# SR1PCB_2024-12-18.net
KiCad netlist of a schematic drawn in Altium Designer
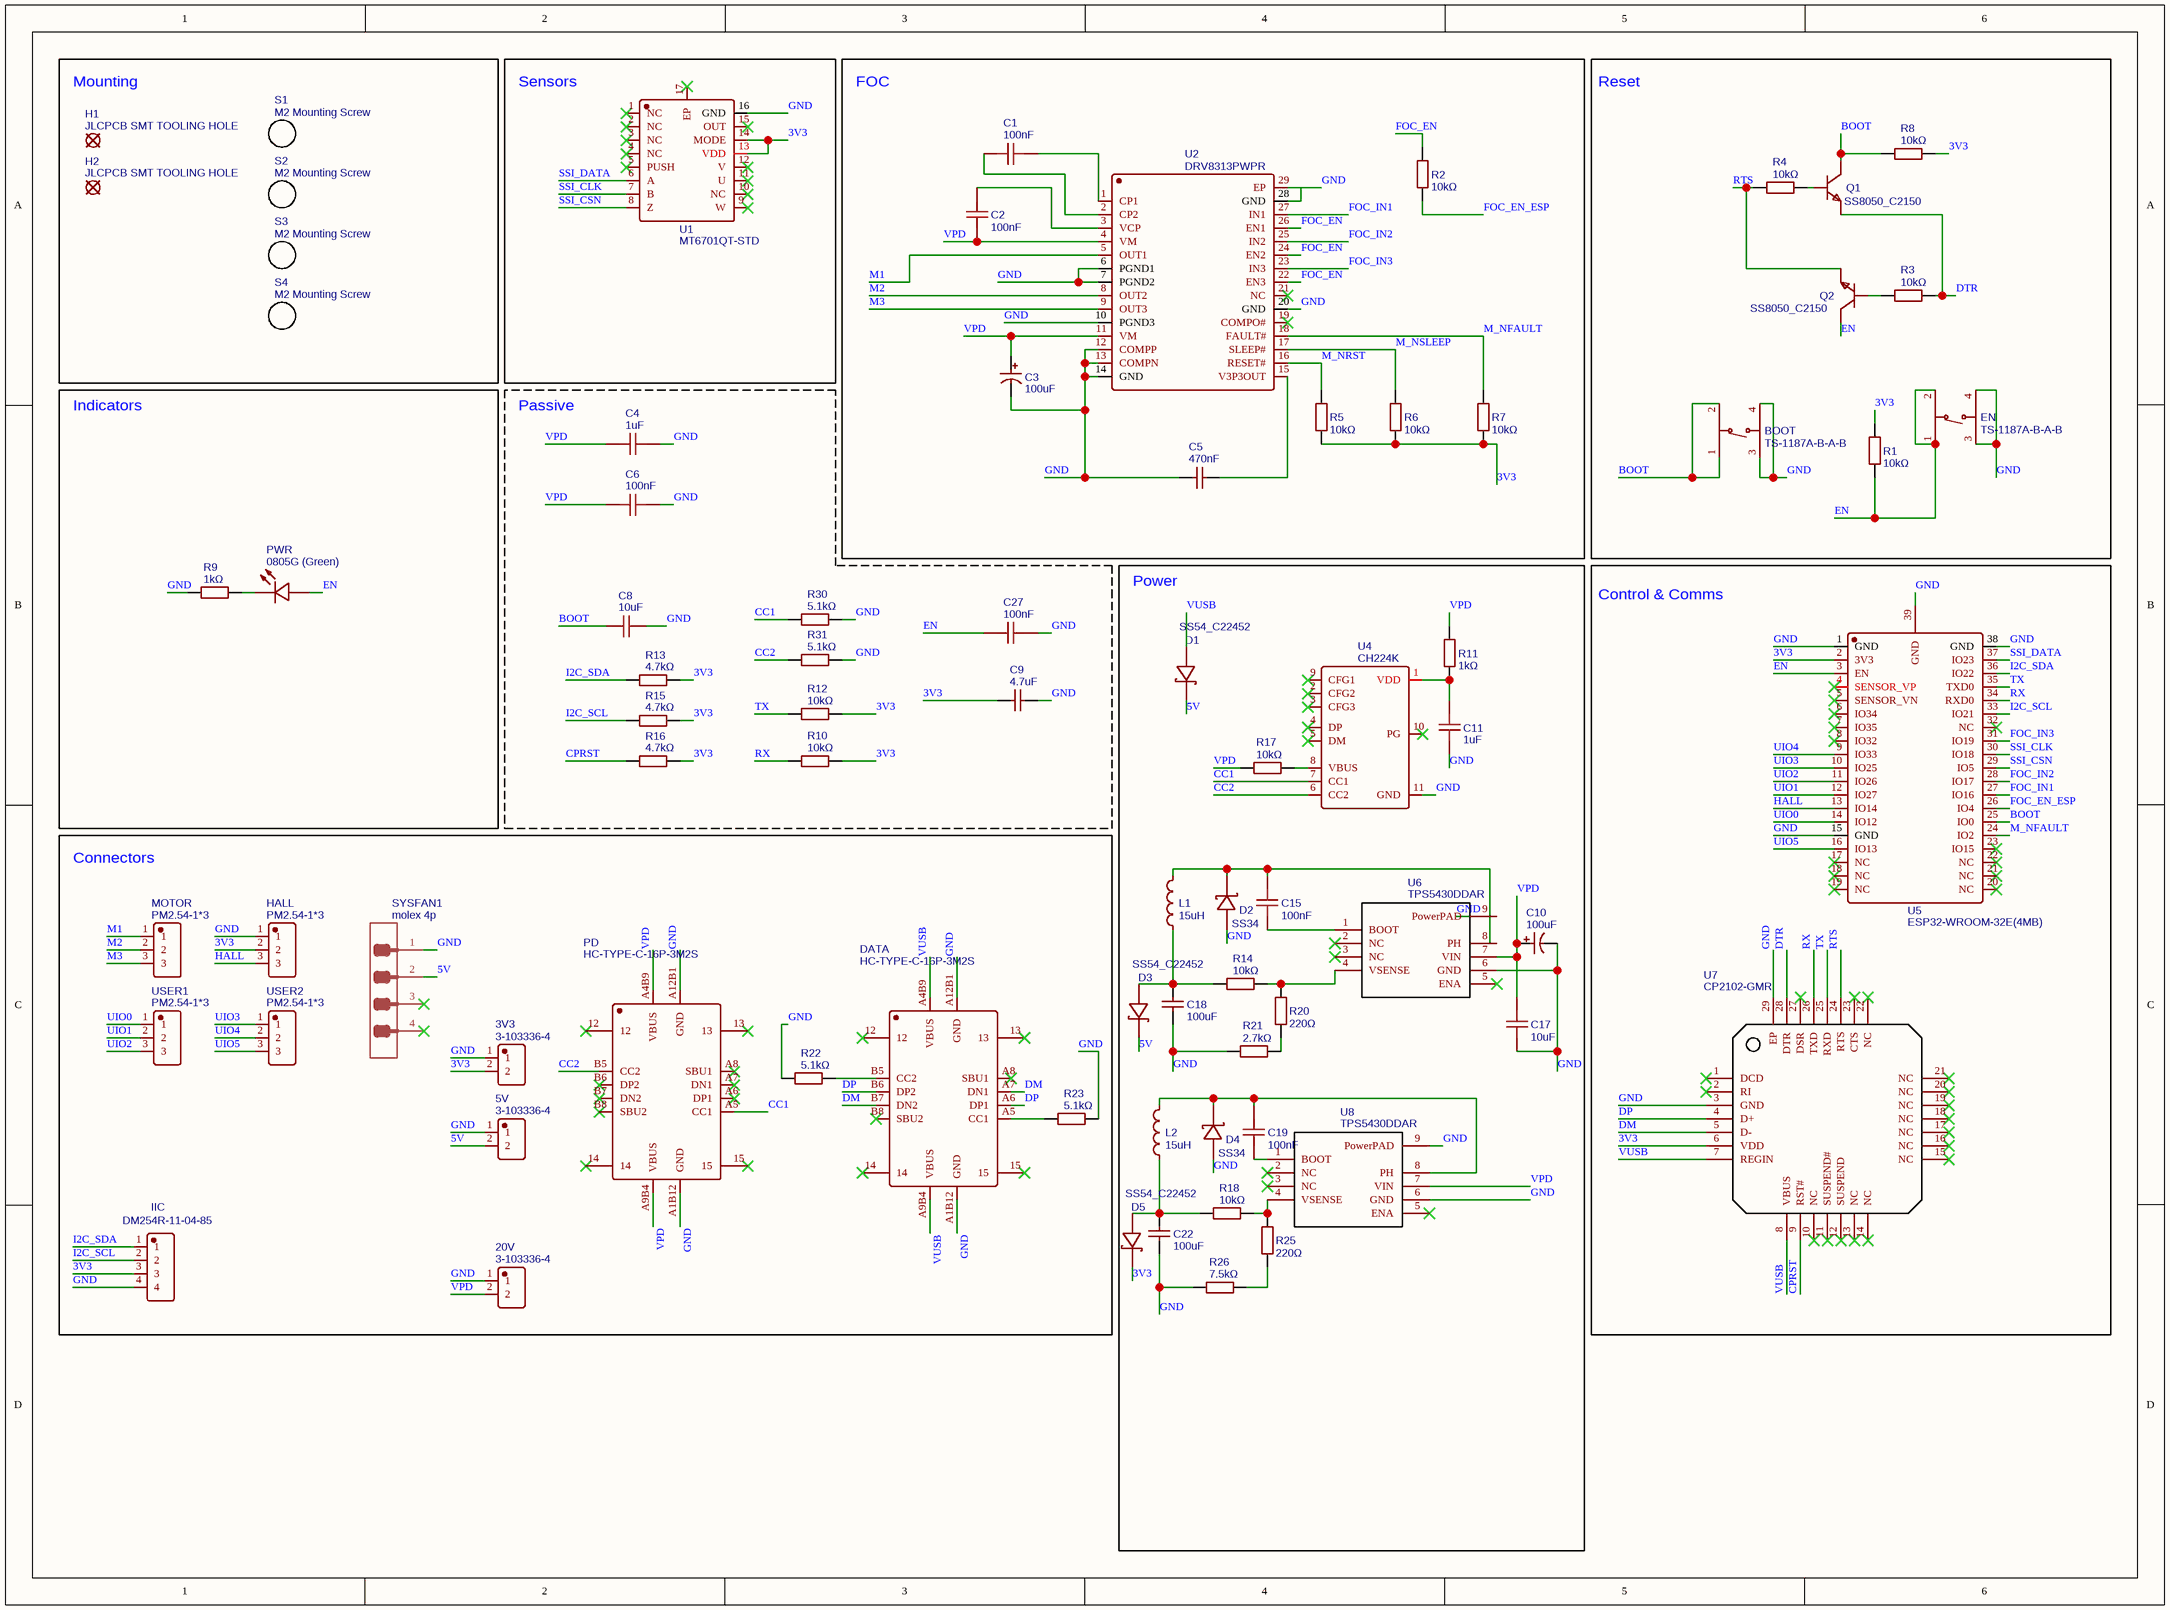
[diagram p0: SR1PCB_2024-12-18.schdoc]

(export (version "E")
  (design (tool "Eeschema 10.0.6"))
  (components
    (comp (ref "3V3")
      (value "3-103336-4")
      (fields (field (name "MANUFACTURER") "TE Connectivity(泰科电子)") (field (name "CONTRIBUTOR") "lcsc"))
      (libsource (lib "altium-import") (part "root_0_3-103336-4_"))
    )
    (comp (ref "5V")
      (value "3-103336-4")
      (fields (field (name "MANUFACTURER") "TE Connectivity(泰科电子)") (field (name "CONTRIBUTOR") "lcsc"))
      (libsource (lib "altium-import") (part "root_0_3-103336-4_"))
    )
    (comp (ref "20V")
      (value "3-103336-4")
      (fields (field (name "MANUFACTURER") "TE Connectivity(泰科电子)") (field (name "CONTRIBUTOR") "lcsc"))
      (libsource (lib "altium-import") (part "root_0_3-103336-4_"))
    )
    (comp (ref "BOOT")
      (value "TS-1187A-B-A-B")
      (fields (field (name "MANUFACTURER") "XKB Connectivity(中国星坤)") (field (name "CONTRIBUTOR") "LCSC"))
      (libsource (lib "altium-import") (part "root_1_TS-1187A-B-A-B_"))
    )
    (comp (ref "C1")
      (value "100nF")
      (fields
        (field (name "MANUFACTURER") "YAGEO(国巨)")
        (field (name "MANUFACTURER PART") "CC0603KRX7R9BB104")
      )
      (libsource (lib "altium-import") (part "root_0_100nF_"))
    )
    (comp (ref "C2")
      (value "100nF")
      (fields
        (field (name "MANUFACTURER") "YAGEO(国巨)")
        (field (name "MANUFACTURER PART") "CC0603KRX7R9BB104")
      )
      (libsource (lib "altium-import") (part "root_1_100nF_"))
    )
    (comp (ref "C3")
      (value "100uF")
      (fields
        (field (name "MANUFACTURER") "ROQANG(容强)")
        (field (name "MANUFACTURER PART") "RT1V101M0607")
        (field (name "CONTRIBUTOR") "LCSC")
      )
      (libsource (lib "altium-import") (part "root_3_100uF_"))
    )
    (comp (ref "C4")
      (value "1uF")
      (fields
        (field (name "MANUFACTURER PART") "CL10A105KB8NNNC")
        (field (name "MANUFACTURER") "SAMSUNG(三星)")
      )
      (libsource (lib "altium-import") (part "root_0_1uF_"))
    )
    (comp (ref "C5")
      (value "470nF")
      (fields
        (field (name "MANUFACTURER PART") "CL21B474KBFNNNE")
        (field (name "MANUFACTURER") "SAMSUNG(三星)")
        (field (name "CONTRIBUTOR") "eisendev")
      )
      (libsource (lib "altium-import") (part "root_3_470nF_"))
    )
    (comp (ref "C6")
      (value "100nF")
      (fields
        (field (name "MANUFACTURER") "YAGEO(国巨)")
        (field (name "MANUFACTURER PART") "CC0603KRX7R9BB104")
      )
      (libsource (lib "altium-import") (part "root_0_100nF_"))
    )
    (comp (ref "C8")
      (value "10uF")
      (fields
        (field (name "MANUFACTURER") "SAMSUNG(三星)")
        (field (name "MANUFACTURER PART") "CL10A106KP8NNNC")
        (field (name "CONTRIBUTOR") "kharchenko.pm")
      )
      (libsource (lib "altium-import") (part "root_0_10uF_"))
    )
    (comp (ref "C9")
      (value "4.7uF")
      (fields
        (field (name "MANUFACTURER PART") "CL05A475MP5NRNC")
        (field (name "MANUFACTURER") "SAMSUNG(三星)")
      )
      (libsource (lib "altium-import") (part "root_0_4.7uF_"))
    )
    (comp (ref "C10")
      (value "100uF")
      (fields
        (field (name "MANUFACTURER") "ROQANG(容强)")
        (field (name "MANUFACTURER PART") "RT1V101M0607")
        (field (name "CONTRIBUTOR") "LCSC")
      )
      (libsource (lib "altium-import") (part "root_0_100uF_"))
    )
    (comp (ref "C11")
      (value "1uF")
      (fields
        (field (name "MANUFACTURER PART") "CL10A105KB8NNNC")
        (field (name "MANUFACTURER") "SAMSUNG(三星)")
      )
      (libsource (lib "altium-import") (part "root_1_1uF_"))
    )
    (comp (ref "C15")
      (value "100nF")
      (fields
        (field (name "MANUFACTURER") "YAGEO(国巨)")
        (field (name "MANUFACTURER PART") "CC0603KRX7R9BB104")
      )
      (libsource (lib "altium-import") (part "root_3_100nF_"))
    )
    (comp (ref "C17")
      (value "10uF")
      (fields
        (field (name "MANUFACTURER PART") "CL21A106KAYNNNE")
        (field (name "MANUFACTURER") "SAMSUNG(三星)")
      )
      (libsource (lib "altium-import") (part "root_1_10uF_"))
    )
    (comp (ref "C18")
      (value "100uF")
      (fields
        (field (name "MANUFACTURER PART") "CL31A107MQHNNNE")
        (field (name "MANUFACTURER") "SAMSUNG(三星)")
      )
      (libsource (lib "altium-import") (part "root_1_100uF_"))
    )
    (comp (ref "C19")
      (value "100nF")
      (fields
        (field (name "MANUFACTURER") "YAGEO(国巨)")
        (field (name "MANUFACTURER PART") "CC0603KRX7R9BB104")
      )
      (libsource (lib "altium-import") (part "root_3_100nF_"))
    )
    (comp (ref "C22")
      (value "100uF")
      (fields
        (field (name "MANUFACTURER PART") "CL31A107MQHNNNE")
        (field (name "MANUFACTURER") "SAMSUNG(三星)")
      )
      (libsource (lib "altium-import") (part "root_1_100uF_"))
    )
    (comp (ref "C27")
      (value "100nF")
      (fields
        (field (name "MANUFACTURER") "YAGEO(国巨)")
        (field (name "MANUFACTURER PART") "CC0603KRX7R9BB104")
      )
      (libsource (lib "altium-import") (part "root_0_100nF_"))
    )
    (comp (ref "D1")
      (value "SS54_C22452")
      (fields
        (field (name "MANUFACTURER PART") "SS54")
        (field (name "MANUFACTURER") "MDD")
        (field (name "CONTRIBUTOR") "mtz8302")
      )
      (libsource (lib "altium-import") (part "root_3_SS54_C22452_"))
    )
    (comp (ref "D2")
      (value "SS34")
      (fields (field (name "MANUFACTURER") "MDD(辰达半导体)"))
      (libsource (lib "altium-import") (part "root_3_SS34_"))
    )
    (comp (ref "D3")
      (value "SS54_C22452")
      (fields
        (field (name "MANUFACTURER PART") "SS54")
        (field (name "MANUFACTURER") "MDD")
        (field (name "CONTRIBUTOR") "mtz8302")
      )
      (libsource (lib "altium-import") (part "root_3_SS54_C22452_"))
    )
    (comp (ref "D4")
      (value "SS34")
      (fields (field (name "MANUFACTURER") "MDD(辰达半导体)"))
      (libsource (lib "altium-import") (part "root_3_SS34_"))
    )
    (comp (ref "D5")
      (value "SS54_C22452")
      (fields
        (field (name "MANUFACTURER PART") "SS54")
        (field (name "MANUFACTURER") "MDD")
        (field (name "CONTRIBUTOR") "mtz8302")
      )
      (libsource (lib "altium-import") (part "root_3_SS54_C22452_"))
    )
    (comp (ref "DATA")
      (value "HC-TYPE-C-16P-3M2S")
      (fields (field (name "MANUFACTURER") "HC(虹成电子)") (field (name "CONTRIBUTOR") "lcsc"))
      (libsource (lib "altium-import") (part "root_0_HC-TYPE-C-16P-3M2S_"))
    )
    (comp (ref "EN")
      (value "TS-1187A-B-A-B")
      (fields (field (name "MANUFACTURER") "XKB Connectivity(中国星坤)") (field (name "CONTRIBUTOR") "LCSC"))
      (libsource (lib "altium-import") (part "root_1_TS-1187A-B-A-B_"))
    )
    (comp (ref "H1")
      (value "JLCPCB SMT TOOLING HOLE")
      (fields (field (name "CONTRIBUTOR") "Sindel90"))
      (libsource (lib "altium-import") (part "root_0_JLCPCB SMT TOOLING HOLE_"))
    )
    (comp (ref "H2")
      (value "JLCPCB SMT TOOLING HOLE")
      (fields (field (name "CONTRIBUTOR") "Sindel90"))
      (libsource (lib "altium-import") (part "root_0_JLCPCB SMT TOOLING HOLE_"))
    )
    (comp (ref "HALL")
      (value "PM2.54-1*3")
      (fields (field (name "MANUFACTURER") "ZHOURI(洲日)") (field (name "CONTRIBUTOR") "lcsc"))
      (libsource (lib "altium-import") (part "root_0_PM2.54-1*3_"))
    )
    (comp (ref "IIC")
      (value "DM254R-11-04-85")
      (fields (field (name "MANUFACTURER") "DEALON(德艺隆)") (field (name "CONTRIBUTOR") "LCSC"))
      (libsource (lib "altium-import") (part "root_0_DM254R-11-04-85_"))
    )
    (comp (ref "L1")
      (value "15uH")
      (fields
        (field (name "MANUFACTURER") "Sunlord(顺络)")
        (field (name "MANUFACTURER PART") "MWSA0603S-150MT")
        (field (name "CONTRIBUTOR") "LCSC")
      )
      (libsource (lib "altium-import") (part "root_1_15uH_"))
    )
    (comp (ref "L2")
      (value "15uH")
      (fields
        (field (name "MANUFACTURER") "Sunlord(顺络)")
        (field (name "MANUFACTURER PART") "MWSA0603S-150MT")
        (field (name "CONTRIBUTOR") "LCSC")
      )
      (libsource (lib "altium-import") (part "root_1_15uH_"))
    )
    (comp (ref "MOTOR")
      (value "PM2.54-1*3")
      (fields (field (name "MANUFACTURER") "ZHOURI(洲日)") (field (name "CONTRIBUTOR") "lcsc"))
      (libsource (lib "altium-import") (part "root_0_PM2.54-1*3_"))
    )
    (comp (ref "PD")
      (value "HC-TYPE-C-16P-3M2S")
      (fields (field (name "MANUFACTURER") "HC(虹成电子)") (field (name "CONTRIBUTOR") "lcsc"))
      (libsource (lib "altium-import") (part "root_0_HC-TYPE-C-16P-3M2S_"))
    )
    (comp (ref "PWR")
      (value "0805G (Green)")
      (fields (field (name "MANUFACTURER") "KENTO") (field (name "MANUFACTURER PART") "KT-0805G"))
      (libsource (lib "altium-import") (part "root_0_0805G (Green)_"))
    )
    (comp (ref "Q1")
      (value "SS8050_C2150")
      (fields (field (name "MANUFACTURER") "CJ(江苏长电/长晶)") (field (name "MANUFACTURER PART") "SS8050"))
      (libsource (lib "altium-import") (part "root_0_SS8050_C2150_"))
    )
    (comp (ref "Q2")
      (value "SS8050_C2150")
      (fields (field (name "MANUFACTURER") "CJ(江苏长电/长晶)") (field (name "MANUFACTURER PART") "SS8050"))
      (libsource (lib "altium-import") (part "root_2_SS8050_C2150_"))
    )
    (comp (ref "R1")
      (value "10kΩ")
      (fields
        (field (name "MANUFACTURER") "UNI-ROYAL(厚声)")
        (field (name "MANUFACTURER PART") "0402WGF1002TCE")
      )
      (libsource (lib "altium-import") (part "root_1_10kΩ_"))
    )
    (comp (ref "R2")
      (value "10kΩ")
      (fields (field (name "MANUFACTURER") "UniOhm") (field (name "MANUFACTURER PART") "0603WAF4701T5E"))
      (libsource (lib "altium-import") (part "root_1_10kΩ_"))
    )
    (comp (ref "R3")
      (value "10kΩ")
      (fields
        (field (name "MANUFACTURER") "UNI-ROYAL(厚声)")
        (field (name "MANUFACTURER PART") "0402WGF1002TCE")
      )
      (libsource (lib "altium-import") (part "root_2_10kΩ_"))
    )
    (comp (ref "R4")
      (value "10kΩ")
      (fields
        (field (name "MANUFACTURER") "UNI-ROYAL(厚声)")
        (field (name "MANUFACTURER PART") "0402WGF1002TCE")
      )
      (libsource (lib "altium-import") (part "root_2_10kΩ_"))
    )
    (comp (ref "R5")
      (value "10kΩ")
      (fields
        (field (name "MANUFACTURER") "UNI-ROYAL(厚声)")
        (field (name "MANUFACTURER PART") "0402WGF1002TCE")
      )
      (libsource (lib "altium-import") (part "root_1_10kΩ_"))
    )
    (comp (ref "R6")
      (value "10kΩ")
      (fields
        (field (name "MANUFACTURER") "UNI-ROYAL(厚声)")
        (field (name "MANUFACTURER PART") "0402WGF1002TCE")
      )
      (libsource (lib "altium-import") (part "root_1_10kΩ_"))
    )
    (comp (ref "R7")
      (value "10kΩ")
      (fields
        (field (name "MANUFACTURER") "UNI-ROYAL(厚声)")
        (field (name "MANUFACTURER PART") "0402WGF1002TCE")
      )
      (libsource (lib "altium-import") (part "root_1_10kΩ_"))
    )
    (comp (ref "R8")
      (value "10kΩ")
      (fields
        (field (name "MANUFACTURER") "UNI-ROYAL(厚声)")
        (field (name "MANUFACTURER PART") "0402WGF1002TCE")
      )
      (libsource (lib "altium-import") (part "root_2_10kΩ_"))
    )
    (comp (ref "R9")
      (value "1kΩ")
      (fields
        (field (name "MANUFACTURER") "UNI-ROYAL(厚声)")
        (field (name "MANUFACTURER PART") "0402WGF1001TCE")
      )
      (libsource (lib "altium-import") (part "root_2_1kΩ_"))
    )
    (comp (ref "R10")
      (value "10kΩ")
      (fields
        (field (name "MANUFACTURER") "UNI-ROYAL(厚声)")
        (field (name "MANUFACTURER PART") "0402WGF1002TCE")
      )
      (libsource (lib "altium-import") (part "root_0_10kΩ_"))
    )
    (comp (ref "R11")
      (value "1kΩ")
      (fields
        (field (name "MANUFACTURER") "UNI-ROYAL(厚声)")
        (field (name "MANUFACTURER PART") "0402WGF1001TCE")
      )
      (libsource (lib "altium-import") (part "root_1_1kΩ_"))
    )
    (comp (ref "R12")
      (value "10kΩ")
      (fields
        (field (name "MANUFACTURER") "UNI-ROYAL(厚声)")
        (field (name "MANUFACTURER PART") "0402WGF1002TCE")
      )
      (libsource (lib "altium-import") (part "root_0_10kΩ_"))
    )
    (comp (ref "R13")
      (value "4.7kΩ")
      (fields
        (field (name "MANUFACTURER") "UNI-ROYAL(厚声)")
        (field (name "MANUFACTURER PART") "0402WGF4701TCE")
      )
      (libsource (lib "altium-import") (part "root_0_4.7kΩ_"))
    )
    (comp (ref "R14")
      (value "10kΩ")
      (fields
        (field (name "MANUFACTURER") "UNI-ROYAL(厚声)")
        (field (name "MANUFACTURER PART") "0402WGF1002TCE")
      )
      (libsource (lib "altium-import") (part "root_0_10kΩ_"))
    )
    (comp (ref "R15")
      (value "4.7kΩ")
      (fields
        (field (name "MANUFACTURER") "UNI-ROYAL(厚声)")
        (field (name "MANUFACTURER PART") "0402WGF4701TCE")
      )
      (libsource (lib "altium-import") (part "root_0_4.7kΩ_"))
    )
    (comp (ref "R16")
      (value "4.7kΩ")
      (fields
        (field (name "MANUFACTURER") "UNI-ROYAL(厚声)")
        (field (name "MANUFACTURER PART") "0402WGF4701TCE")
      )
      (libsource (lib "altium-import") (part "root_0_4.7kΩ_"))
    )
    (comp (ref "R17")
      (value "10kΩ")
      (fields
        (field (name "MANUFACTURER") "UNI-ROYAL(厚声)")
        (field (name "MANUFACTURER PART") "0402WGF1002TCE")
      )
      (libsource (lib "altium-import") (part "root_2_10kΩ_"))
    )
    (comp (ref "R18")
      (value "10kΩ")
      (fields
        (field (name "MANUFACTURER") "UNI-ROYAL(厚声)")
        (field (name "MANUFACTURER PART") "0402WGF1002TCE")
      )
      (libsource (lib "altium-import") (part "root_0_10kΩ_"))
    )
    (comp (ref "R20")
      (value "220Ω")
      (fields
        (field (name "MANUFACTURER") "UNI-ROYAL(厚声)")
        (field (name "MANUFACTURER PART") "0603WAF2200T5E")
      )
      (libsource (lib "altium-import") (part "root_1_220Ω_"))
    )
    (comp (ref "R21")
      (value "2.7kΩ")
      (fields
        (field (name "MANUFACTURER") "UniOhm")
        (field (name "MANUFACTURER PART") "0603WAF2701T5E")
        (field (name "CONTRIBUTOR") "kliu24")
      )
      (libsource (lib "altium-import") (part "root_0_2.7kΩ_"))
    )
    (comp (ref "R22")
      (value "5.1kΩ")
      (fields
        (field (name "MANUFACTURER") "UNI-ROYAL(厚声)")
        (field (name "MANUFACTURER PART") "0402WGF5101TCE")
      )
      (libsource (lib "altium-import") (part "root_0_5.1kΩ_"))
    )
    (comp (ref "R23")
      (value "5.1kΩ")
      (fields
        (field (name "MANUFACTURER") "UNI-ROYAL(厚声)")
        (field (name "MANUFACTURER PART") "0402WGF5101TCE")
      )
      (libsource (lib "altium-import") (part "root_0_5.1kΩ_"))
    )
    (comp (ref "R25")
      (value "220Ω")
      (fields
        (field (name "MANUFACTURER") "UNI-ROYAL(厚声)")
        (field (name "MANUFACTURER PART") "0603WAF2200T5E")
      )
      (libsource (lib "altium-import") (part "root_1_220Ω_"))
    )
    (comp (ref "R26")
      (value "7.5kΩ")
      (fields
        (field (name "MANUFACTURER") "UniOhm")
        (field (name "MANUFACTURER PART") "0603WAF7501T5E")
        (field (name "CONTRIBUTOR") "kliu24")
      )
      (libsource (lib "altium-import") (part "root_1_7.5kΩ_"))
    )
    (comp (ref "R30")
      (value "5.1kΩ")
      (fields
        (field (name "MANUFACTURER") "UNI-ROYAL(厚声)")
        (field (name "MANUFACTURER PART") "0402WGF5101TCE")
      )
      (libsource (lib "altium-import") (part "root_0_5.1kΩ_"))
    )
    (comp (ref "R31")
      (value "5.1kΩ")
      (fields
        (field (name "MANUFACTURER") "UNI-ROYAL(厚声)")
        (field (name "MANUFACTURER PART") "0402WGF5101TCE")
      )
      (libsource (lib "altium-import") (part "root_0_5.1kΩ_"))
    )
    (comp (ref "S1")
      (value "M2 Mounting Screw")
      (fields (field (name "CONTRIBUTOR") "Dayat -"))
      (libsource (lib "altium-import") (part "root_0_M2 Mounting Screw_"))
    )
    (comp (ref "S2")
      (value "M2 Mounting Screw")
      (fields (field (name "CONTRIBUTOR") "Dayat -"))
      (libsource (lib "altium-import") (part "root_0_M2 Mounting Screw_"))
    )
    (comp (ref "S3")
      (value "M2 Mounting Screw")
      (fields (field (name "CONTRIBUTOR") "Dayat -"))
      (libsource (lib "altium-import") (part "root_0_M2 Mounting Screw_"))
    )
    (comp (ref "S4")
      (value "M2 Mounting Screw")
      (fields (field (name "CONTRIBUTOR") "Dayat -"))
      (libsource (lib "altium-import") (part "root_0_M2 Mounting Screw_"))
    )
    (comp (ref "SYSFAN1")
      (value "molex 4p")
      (fields (field (name "CONTRIBUTOR") "delil1220"))
      (libsource (lib "altium-import") (part "root_0_molex 4p_"))
    )
    (comp (ref "U1")
      (value "MT6701QT-STD")
      (fields (field (name "MANUFACTURER") "MagnTek(麦歌恩)") (field (name "CONTRIBUTOR") "LCSC"))
      (libsource (lib "altium-import") (part "root_0_MT6701QT-STD_"))
    )
    (comp (ref "U2")
      (value "DRV8313PWPR")
      (fields (field (name "MANUFACTURER") "Texas Instruments") (field (name "CONTRIBUTOR") "LCSC"))
      (libsource (lib "altium-import") (part "root_0_DRV8313PWPR_"))
    )
    (comp (ref "U4")
      (value "CH224K")
      (fields (field (name "MANUFACTURER") "WCH(南京沁恒)") (field (name "CONTRIBUTOR") "lcsc"))
      (libsource (lib "altium-import") (part "root_0_CH224K_"))
    )
    (comp (ref "U5")
      (value "ESP32-WROOM-32E(4MB)")
      (fields
        (field (name "MANUFACTURER") "ESPRESSIF(乐鑫)")
        (field (name "MANUFACTURER PART") "ESP32-WROOM-32E-N4")
        (field (name "CONTRIBUTOR") "LCSC")
      )
      (libsource (lib "altium-import") (part "root_0_ESP32-WROOM-32E(4MB)_"))
    )
    (comp (ref "U6")
      (value "TPS5430DDAR")
      (fields (field (name "MANUFACTURER") "TI(德州仪器)"))
      (libsource (lib "altium-import") (part "root_0_TPS5430DDAR_"))
    )
    (comp (ref "U7")
      (value "CP2102-GMR")
      (fields (field (name "MANUFACTURER") "SKYWORKS/SILICON LABS(芯科)"))
      (libsource (lib "altium-import") (part "root_0_CP2102-GMR_"))
    )
    (comp (ref "U8")
      (value "TPS5430DDAR")
      (fields (field (name "MANUFACTURER") "TI(德州仪器)"))
      (libsource (lib "altium-import") (part "root_0_TPS5430DDAR_"))
    )
    (comp (ref "USER1")
      (value "PM2.54-1*3")
      (fields (field (name "MANUFACTURER") "ZHOURI(洲日)") (field (name "CONTRIBUTOR") "lcsc"))
      (libsource (lib "altium-import") (part "root_0_PM2.54-1*3_"))
    )
    (comp (ref "USER2")
      (value "PM2.54-1*3")
      (fields (field (name "MANUFACTURER") "ZHOURI(洲日)") (field (name "CONTRIBUTOR") "lcsc"))
      (libsource (lib "altium-import") (part "root_0_PM2.54-1*3_"))
    )
  )
  (nets
    (net (code "1") (name "/3V3") (class "Default")
      (node (ref "3V3") (pin "2") (pinfunction "2_2") (pintype "passive"))
      (node (ref "C9") (pin "1") (pinfunction "1_1") (pintype "passive"))
      (node (ref "D5") (pin "2") (pinfunction "K_2") (pintype "passive"))
      (node (ref "HALL") (pin "2") (pinfunction "2_2") (pintype "passive"))
      (node (ref "IIC") (pin "3") (pinfunction "3_3") (pintype "passive"))
      (node (ref "R1") (pin "2") (pinfunction "2_2") (pintype "passive"))
      (node (ref "R10") (pin "2") (pinfunction "2_2") (pintype "passive"))
      (node (ref "R12") (pin "2") (pinfunction "2_2") (pintype "passive"))
      (node (ref "R13") (pin "2") (pinfunction "2_2") (pintype "passive"))
      (node (ref "R15") (pin "2") (pinfunction "2_2") (pintype "passive"))
      (node (ref "R16") (pin "2") (pinfunction "2_2") (pintype "passive"))
      (node (ref "R5") (pin "1") (pinfunction "1_1") (pintype "passive"))
      (node (ref "R6") (pin "1") (pinfunction "1_1") (pintype "passive"))
      (node (ref "R7") (pin "1") (pinfunction "1_1") (pintype "passive"))
      (node (ref "R8") (pin "1") (pinfunction "1_1") (pintype "passive"))
      (node (ref "U1") (pin "13") (pinfunction "VDD_13") (pintype "passive"))
      (node (ref "U1") (pin "14") (pinfunction "MODE_14") (pintype "passive"))
      (node (ref "U5") (pin "2") (pinfunction "3V3_2") (pintype "passive"))
      (node (ref "U7") (pin "6") (pinfunction "VDD_6") (pintype "passive"))
    )
    (net (code "2") (name "/5V") (class "Default")
      (node (ref "5V") (pin "2") (pinfunction "2_2") (pintype "passive"))
      (node (ref "D1") (pin "2") (pinfunction "K_2") (pintype "passive"))
      (node (ref "D3") (pin "2") (pinfunction "K_2") (pintype "passive"))
      (node (ref "SYSFAN1") (pin "2") (pinfunction "2_2") (pintype "passive"))
    )
    (net (code "3") (name "/BOOT") (class "Default")
      (node (ref "BOOT") (pin "1") (pinfunction "A_1") (pintype "passive"))
      (node (ref "BOOT") (pin "2") (pinfunction "B_2") (pintype "passive"))
      (node (ref "C8") (pin "1") (pinfunction "1_1") (pintype "passive"))
      (node (ref "Q1") (pin "3") (pinfunction "C_3") (pintype "passive"))
      (node (ref "R8") (pin "2") (pinfunction "2_2") (pintype "passive"))
      (node (ref "U5") (pin "25") (pinfunction "IO0_25") (pintype "passive"))
    )
    (net (code "4") (name "/CC1") (class "Default")
      (node (ref "PD") (pin "A5") (pinfunction "CC1_A5") (pintype "passive"))
      (node (ref "R30") (pin "1") (pinfunction "1_1") (pintype "passive"))
      (node (ref "U4") (pin "7") (pinfunction "CC1_7") (pintype "passive"))
    )
    (net (code "5") (name "/CC2") (class "Default")
      (node (ref "PD") (pin "B5") (pinfunction "CC2_B5") (pintype "passive"))
      (node (ref "R31") (pin "1") (pinfunction "1_1") (pintype "passive"))
      (node (ref "U4") (pin "6") (pinfunction "CC2_6") (pintype "passive"))
    )
    (net (code "6") (name "/CPRST") (class "Default")
      (node (ref "R16") (pin "1") (pinfunction "1_1") (pintype "passive"))
      (node (ref "U7") (pin "9") (pinfunction "RST#_9") (pintype "passive"))
    )
    (net (code "7") (name "/DM") (class "Default")
      (node (ref "DATA") (pin "A7") (pinfunction "DN1_A7") (pintype "passive"))
      (node (ref "DATA") (pin "B7") (pinfunction "DN2_B7") (pintype "passive"))
      (node (ref "U7") (pin "5") (pinfunction "D-_5") (pintype "passive"))
    )
    (net (code "8") (name "/DP") (class "Default")
      (node (ref "DATA") (pin "A6") (pinfunction "DP1_A6") (pintype "passive"))
      (node (ref "DATA") (pin "B6") (pinfunction "DP2_B6") (pintype "passive"))
      (node (ref "U7") (pin "4") (pinfunction "D+_4") (pintype "passive"))
    )
    (net (code "9") (name "/DTR") (class "Default")
      (node (ref "Q1") (pin "2") (pinfunction "E_2") (pintype "passive"))
      (node (ref "R3") (pin "1") (pinfunction "1_1") (pintype "passive"))
      (node (ref "U7") (pin "28") (pinfunction "DTR_28") (pintype "passive"))
    )
    (net (code "10") (name "/EN") (class "Default")
      (node (ref "C27") (pin "1") (pinfunction "1_1") (pintype "passive"))
      (node (ref "EN") (pin "1") (pinfunction "A_1") (pintype "passive"))
      (node (ref "EN") (pin "2") (pinfunction "B_2") (pintype "passive"))
      (node (ref "PWR") (pin "1") (pinfunction "A_1") (pintype "passive"))
      (node (ref "Q2") (pin "3") (pinfunction "C_3") (pintype "passive"))
      (node (ref "R1") (pin "1") (pinfunction "1_1") (pintype "passive"))
      (node (ref "U5") (pin "3") (pinfunction "EN_3") (pintype "passive"))
    )
    (net (code "11") (name "/FOC_EN") (class "Default")
      (node (ref "R2") (pin "2") (pinfunction "2_2") (pintype "passive"))
      (node (ref "U2") (pin "22") (pinfunction "EN3_22") (pintype "passive"))
      (node (ref "U2") (pin "24") (pinfunction "EN2_24") (pintype "passive"))
      (node (ref "U2") (pin "26") (pinfunction "EN1_26") (pintype "passive"))
    )
    (net (code "12") (name "/FOC_EN_ESP") (class "Default")
      (node (ref "R2") (pin "1") (pinfunction "1_1") (pintype "passive"))
      (node (ref "U5") (pin "26") (pinfunction "IO4_26") (pintype "passive"))
    )
    (net (code "13") (name "/FOC_IN1") (class "Default")
      (node (ref "U2") (pin "27") (pinfunction "IN1_27") (pintype "passive"))
      (node (ref "U5") (pin "27") (pinfunction "IO16_27") (pintype "passive"))
    )
    (net (code "14") (name "/FOC_IN2") (class "Default")
      (node (ref "U2") (pin "25") (pinfunction "IN2_25") (pintype "passive"))
      (node (ref "U5") (pin "28") (pinfunction "IO17_28") (pintype "passive"))
    )
    (net (code "15") (name "/FOC_IN3") (class "Default")
      (node (ref "U2") (pin "23") (pinfunction "IN3_23") (pintype "passive"))
      (node (ref "U5") (pin "31") (pinfunction "IO19_31") (pintype "passive"))
    )
    (net (code "16") (name "/GND") (class "Default")
      (node (ref "20V") (pin "1") (pinfunction "1_1") (pintype "passive"))
      (node (ref "3V3") (pin "1") (pinfunction "1_1") (pintype "passive"))
      (node (ref "5V") (pin "1") (pinfunction "1_1") (pintype "passive"))
      (node (ref "BOOT") (pin "3") (pinfunction "C_3") (pintype "passive"))
      (node (ref "BOOT") (pin "4") (pinfunction "D_4") (pintype "passive"))
      (node (ref "C10") (pin "2") (pinfunction "2_2") (pintype "passive"))
      (node (ref "C11") (pin "1") (pinfunction "1_1") (pintype "passive"))
      (node (ref "C17") (pin "1") (pinfunction "1_1") (pintype "passive"))
      (node (ref "C18") (pin "1") (pinfunction "1_1") (pintype "passive"))
      (node (ref "C22") (pin "1") (pinfunction "1_1") (pintype "passive"))
      (node (ref "C27") (pin "2") (pinfunction "2_2") (pintype "passive"))
      (node (ref "C3") (pin "2") (pinfunction "2_2") (pintype "passive"))
      (node (ref "C4") (pin "2") (pinfunction "2_2") (pintype "passive"))
      (node (ref "C5") (pin "1") (pinfunction "1_1") (pintype "passive"))
      (node (ref "C6") (pin "2") (pinfunction "2_2") (pintype "passive"))
      (node (ref "C8") (pin "2") (pinfunction "2_2") (pintype "passive"))
      (node (ref "C9") (pin "2") (pinfunction "2_2") (pintype "passive"))
      (node (ref "D2") (pin "2") (pinfunction "A_2") (pintype "passive"))
      (node (ref "D4") (pin "2") (pinfunction "A_2") (pintype "passive"))
      (node (ref "DATA") (pin "A12B1") (pinfunction "GND_A12B1") (pintype "passive"))
      (node (ref "DATA") (pin "A1B12") (pinfunction "GND_A1B12") (pintype "passive"))
      (node (ref "EN") (pin "3") (pinfunction "C_3") (pintype "passive"))
      (node (ref "EN") (pin "4") (pinfunction "D_4") (pintype "passive"))
      (node (ref "HALL") (pin "1") (pinfunction "1_1") (pintype "passive"))
      (node (ref "IIC") (pin "4") (pinfunction "4_4") (pintype "passive"))
      (node (ref "PD") (pin "A12B1") (pinfunction "GND_A12B1") (pintype "passive"))
      (node (ref "PD") (pin "A1B12") (pinfunction "GND_A1B12") (pintype "passive"))
      (node (ref "R21") (pin "2") (pinfunction "2_2") (pintype "passive"))
      (node (ref "R22") (pin "1") (pinfunction "1_1") (pintype "passive"))
      (node (ref "R23") (pin "2") (pinfunction "2_2") (pintype "passive"))
      (node (ref "R26") (pin "2") (pinfunction "2_2") (pintype "passive"))
      (node (ref "R30") (pin "2") (pinfunction "2_2") (pintype "passive"))
      (node (ref "R31") (pin "2") (pinfunction "2_2") (pintype "passive"))
      (node (ref "R9") (pin "2") (pinfunction "2_2") (pintype "passive"))
      (node (ref "SYSFAN1") (pin "1") (pinfunction "1_1") (pintype "passive"))
      (node (ref "U1") (pin "16") (pinfunction "GND_16") (pintype "passive"))
      (node (ref "U2") (pin "10") (pinfunction "PGND3_10") (pintype "passive"))
      (node (ref "U2") (pin "12") (pinfunction "COMPP_12") (pintype "passive"))
      (node (ref "U2") (pin "13") (pinfunction "COMPN_13") (pintype "passive"))
      (node (ref "U2") (pin "14") (pinfunction "GND_14") (pintype "passive"))
      (node (ref "U2") (pin "20") (pinfunction "GND_20") (pintype "passive"))
      (node (ref "U2") (pin "28") (pinfunction "GND_28") (pintype "passive"))
      (node (ref "U2") (pin "29") (pinfunction "EP_29") (pintype "passive"))
      (node (ref "U2") (pin "6") (pinfunction "PGND1_6") (pintype "passive"))
      (node (ref "U2") (pin "7") (pinfunction "PGND2_7") (pintype "passive"))
      (node (ref "U4") (pin "11") (pinfunction "GND_11") (pintype "passive"))
      (node (ref "U5") (pin "1") (pinfunction "GND_1") (pintype "passive"))
      (node (ref "U5") (pin "15") (pinfunction "GND_15") (pintype "passive"))
      (node (ref "U5") (pin "38") (pinfunction "GND_38") (pintype "passive"))
      (node (ref "U5") (pin "39") (pinfunction "GND_39") (pintype "passive"))
      (node (ref "U6") (pin "6") (pinfunction "GND_6") (pintype "passive"))
      (node (ref "U6") (pin "9") (pinfunction "PowerPAD_9") (pintype "passive"))
      (node (ref "U7") (pin "29") (pinfunction "EP_29") (pintype "passive"))
      (node (ref "U7") (pin "3") (pinfunction "GND_3") (pintype "passive"))
      (node (ref "U8") (pin "6") (pinfunction "GND_6") (pintype "passive"))
      (node (ref "U8") (pin "9") (pinfunction "PowerPAD_9") (pintype "passive"))
    )
    (net (code "17") (name "/HALL") (class "Default")
      (node (ref "HALL") (pin "3") (pinfunction "3_3") (pintype "passive"))
      (node (ref "U5") (pin "13") (pinfunction "IO14_13") (pintype "passive"))
    )
    (net (code "18") (name "/I2C_SCL") (class "Default")
      (node (ref "IIC") (pin "2") (pinfunction "2_2") (pintype "passive"))
      (node (ref "R15") (pin "1") (pinfunction "1_1") (pintype "passive"))
      (node (ref "U5") (pin "33") (pinfunction "IO21_33") (pintype "passive"))
    )
    (net (code "19") (name "/I2C_SDA") (class "Default")
      (node (ref "IIC") (pin "1") (pinfunction "1_1") (pintype "passive"))
      (node (ref "R13") (pin "1") (pinfunction "1_1") (pintype "passive"))
      (node (ref "U5") (pin "36") (pinfunction "IO22_36") (pintype "passive"))
    )
    (net (code "20") (name "/M1") (class "Default")
      (node (ref "MOTOR") (pin "1") (pinfunction "1_1") (pintype "passive"))
      (node (ref "U2") (pin "5") (pinfunction "OUT1_5") (pintype "passive"))
    )
    (net (code "21") (name "/M2") (class "Default")
      (node (ref "MOTOR") (pin "2") (pinfunction "2_2") (pintype "passive"))
      (node (ref "U2") (pin "8") (pinfunction "OUT2_8") (pintype "passive"))
    )
    (net (code "22") (name "/M3") (class "Default")
      (node (ref "MOTOR") (pin "3") (pinfunction "3_3") (pintype "passive"))
      (node (ref "U2") (pin "9") (pinfunction "OUT3_9") (pintype "passive"))
    )
    (net (code "23") (name "/M_NFAULT") (class "Default")
      (node (ref "R7") (pin "2") (pinfunction "2_2") (pintype "passive"))
      (node (ref "U2") (pin "18") (pinfunction "FAULT#_18") (pintype "passive"))
      (node (ref "U5") (pin "24") (pinfunction "IO2_24") (pintype "passive"))
    )
    (net (code "24") (name "/M_NRST") (class "Default")
      (node (ref "R5") (pin "2") (pinfunction "2_2") (pintype "passive"))
      (node (ref "U2") (pin "16") (pinfunction "RESET#_16") (pintype "passive"))
    )
    (net (code "25") (name "/M_NSLEEP") (class "Default")
      (node (ref "R6") (pin "2") (pinfunction "2_2") (pintype "passive"))
      (node (ref "U2") (pin "17") (pinfunction "SLEEP#_17") (pintype "passive"))
    )
    (net (code "26") (name "/RTS") (class "Default")
      (node (ref "Q2") (pin "2") (pinfunction "E_2") (pintype "passive"))
      (node (ref "R4") (pin "2") (pinfunction "2_2") (pintype "passive"))
      (node (ref "U7") (pin "24") (pinfunction "RTS_24") (pintype "passive"))
    )
    (net (code "27") (name "/RX") (class "Default")
      (node (ref "R10") (pin "1") (pinfunction "1_1") (pintype "passive"))
      (node (ref "U5") (pin "34") (pinfunction "RXD0_34") (pintype "passive"))
      (node (ref "U7") (pin "26") (pinfunction "TXD_26") (pintype "passive"))
    )
    (net (code "28") (name "/SSI_CLK") (class "Default")
      (node (ref "U1") (pin "7") (pinfunction "B_7") (pintype "passive"))
      (node (ref "U5") (pin "30") (pinfunction "IO18_30") (pintype "passive"))
    )
    (net (code "29") (name "/SSI_CSN") (class "Default")
      (node (ref "U1") (pin "8") (pinfunction "Z_8") (pintype "passive"))
      (node (ref "U5") (pin "29") (pinfunction "IO5_29") (pintype "passive"))
    )
    (net (code "30") (name "/SSI_DATA") (class "Default")
      (node (ref "U1") (pin "6") (pinfunction "A_6") (pintype "passive"))
      (node (ref "U5") (pin "37") (pinfunction "IO23_37") (pintype "passive"))
    )
    (net (code "31") (name "/TX") (class "Default")
      (node (ref "R12") (pin "1") (pinfunction "1_1") (pintype "passive"))
      (node (ref "U5") (pin "35") (pinfunction "TXD0_35") (pintype "passive"))
      (node (ref "U7") (pin "25") (pinfunction "RXD_25") (pintype "passive"))
    )
    (net (code "32") (name "/UIO0") (class "Default")
      (node (ref "U5") (pin "14") (pinfunction "IO12_14") (pintype "passive"))
      (node (ref "USER1") (pin "1") (pinfunction "1_1") (pintype "passive"))
    )
    (net (code "33") (name "/UIO1") (class "Default")
      (node (ref "U5") (pin "12") (pinfunction "IO27_12") (pintype "passive"))
      (node (ref "USER1") (pin "2") (pinfunction "2_2") (pintype "passive"))
    )
    (net (code "34") (name "/UIO2") (class "Default")
      (node (ref "U5") (pin "11") (pinfunction "IO26_11") (pintype "passive"))
      (node (ref "USER1") (pin "3") (pinfunction "3_3") (pintype "passive"))
    )
    (net (code "35") (name "/UIO3") (class "Default")
      (node (ref "U5") (pin "10") (pinfunction "IO25_10") (pintype "passive"))
      (node (ref "USER2") (pin "1") (pinfunction "1_1") (pintype "passive"))
    )
    (net (code "36") (name "/UIO4") (class "Default")
      (node (ref "U5") (pin "9") (pinfunction "IO33_9") (pintype "passive"))
      (node (ref "USER2") (pin "2") (pinfunction "2_2") (pintype "passive"))
    )
    (net (code "37") (name "/UIO5") (class "Default")
      (node (ref "U5") (pin "16") (pinfunction "IO13_16") (pintype "passive"))
      (node (ref "USER2") (pin "3") (pinfunction "3_3") (pintype "passive"))
    )
    (net (code "38") (name "/VPD") (class "Default")
      (node (ref "20V") (pin "2") (pinfunction "2_2") (pintype "passive"))
      (node (ref "C10") (pin "1") (pinfunction "1_1") (pintype "passive"))
      (node (ref "C17") (pin "2") (pinfunction "2_2") (pintype "passive"))
      (node (ref "C2") (pin "1") (pinfunction "1_1") (pintype "passive"))
      (node (ref "C3") (pin "1") (pinfunction "1_1") (pintype "passive"))
      (node (ref "C4") (pin "1") (pinfunction "1_1") (pintype "passive"))
      (node (ref "C6") (pin "1") (pinfunction "1_1") (pintype "passive"))
      (node (ref "PD") (pin "A4B9") (pinfunction "VBUS_A4B9") (pintype "passive"))
      (node (ref "PD") (pin "A9B4") (pinfunction "VBUS_A9B4") (pintype "passive"))
      (node (ref "R11") (pin "2") (pinfunction "2_2") (pintype "passive"))
      (node (ref "R17") (pin "2") (pinfunction "2_2") (pintype "passive"))
      (node (ref "U2") (pin "11") (pinfunction "VM_11") (pintype "passive"))
      (node (ref "U2") (pin "4") (pinfunction "VM_4") (pintype "passive"))
      (node (ref "U6") (pin "7") (pinfunction "VIN_7") (pintype "passive"))
      (node (ref "U8") (pin "7") (pinfunction "VIN_7") (pintype "passive"))
    )
    (net (code "39") (name "/VUSB") (class "Default")
      (node (ref "D1") (pin "1") (pinfunction "A_1") (pintype "passive"))
      (node (ref "DATA") (pin "A4B9") (pinfunction "VBUS_A4B9") (pintype "passive"))
      (node (ref "DATA") (pin "A9B4") (pinfunction "VBUS_A9B4") (pintype "passive"))
      (node (ref "U7") (pin "7") (pinfunction "REGIN_7") (pintype "passive"))
      (node (ref "U7") (pin "8") (pinfunction "VBUS_8") (pintype "passive"))
    )
    (net (code "40") (name "Net-(D2-K)") (class "Default")
      (node (ref "C15") (pin "1") (pinfunction "1_1") (pintype "passive"))
      (node (ref "D2") (pin "1") (pinfunction "K_1") (pintype "passive"))
      (node (ref "L1") (pin "2") (pinfunction "2_2") (pintype "passive"))
      (node (ref "U6") (pin "8") (pinfunction "PH_8") (pintype "passive"))
    )
    (net (code "41") (name "Net-(D3-A)") (class "Default")
      (node (ref "C18") (pin "2") (pinfunction "2_2") (pintype "passive"))
      (node (ref "D3") (pin "1") (pinfunction "A_1") (pintype "passive"))
      (node (ref "L1") (pin "1") (pinfunction "1_1") (pintype "passive"))
      (node (ref "R14") (pin "1") (pinfunction "1_1") (pintype "passive"))
    )
    (net (code "42") (name "Net-(D4-K)") (class "Default")
      (node (ref "C19") (pin "1") (pinfunction "1_1") (pintype "passive"))
      (node (ref "D4") (pin "1") (pinfunction "K_1") (pintype "passive"))
      (node (ref "L2") (pin "2") (pinfunction "2_2") (pintype "passive"))
      (node (ref "U8") (pin "8") (pinfunction "PH_8") (pintype "passive"))
    )
    (net (code "43") (name "Net-(D5-A)") (class "Default")
      (node (ref "C22") (pin "2") (pinfunction "2_2") (pintype "passive"))
      (node (ref "D5") (pin "1") (pinfunction "A_1") (pintype "passive"))
      (node (ref "L2") (pin "1") (pinfunction "1_1") (pintype "passive"))
      (node (ref "R18") (pin "1") (pinfunction "1_1") (pintype "passive"))
    )
    (net (code "44") (name "Net-(DATA-CC1)") (class "Default")
      (node (ref "DATA") (pin "A5") (pinfunction "CC1_A5") (pintype "passive"))
      (node (ref "R23") (pin "1") (pinfunction "1_1") (pintype "passive"))
    )
    (net (code "45") (name "Net-(DATA-CC2)") (class "Default")
      (node (ref "DATA") (pin "B5") (pinfunction "CC2_B5") (pintype "passive"))
      (node (ref "R22") (pin "2") (pinfunction "2_2") (pintype "passive"))
    )
    (net (code "46") (name "Net-(PWR-K)") (class "Default")
      (node (ref "PWR") (pin "2") (pinfunction "K_2") (pintype "passive"))
      (node (ref "R9") (pin "1") (pinfunction "1_1") (pintype "passive"))
    )
    (net (code "47") (name "Net-(Q1-B)") (class "Default")
      (node (ref "Q1") (pin "1") (pinfunction "B_1") (pintype "passive"))
      (node (ref "R4") (pin "1") (pinfunction "1_1") (pintype "passive"))
    )
    (net (code "48") (name "Net-(Q2-B)") (class "Default")
      (node (ref "Q2") (pin "1") (pinfunction "B_1") (pintype "passive"))
      (node (ref "R3") (pin "2") (pinfunction "2_2") (pintype "passive"))
    )
    (net (code "49") (name "Net-(R20-Pad1)") (class "Default")
      (node (ref "R20") (pin "1") (pinfunction "1_1") (pintype "passive"))
      (node (ref "R21") (pin "1") (pinfunction "1_1") (pintype "passive"))
    )
    (net (code "50") (name "Net-(R25-Pad1)") (class "Default")
      (node (ref "R25") (pin "1") (pinfunction "1_1") (pintype "passive"))
      (node (ref "R26") (pin "1") (pinfunction "1_1") (pintype "passive"))
    )
    (net (code "51") (name "Net-(U2-CP1)") (class "Default")
      (node (ref "C1") (pin "2") (pinfunction "2_2") (pintype "passive"))
      (node (ref "U2") (pin "1") (pinfunction "CP1_1") (pintype "passive"))
    )
    (net (code "52") (name "Net-(U2-CP2)") (class "Default")
      (node (ref "C1") (pin "1") (pinfunction "1_1") (pintype "passive"))
      (node (ref "U2") (pin "2") (pinfunction "CP2_2") (pintype "passive"))
    )
    (net (code "53") (name "Net-(U2-V3P3OUT)") (class "Default")
      (node (ref "C5") (pin "2") (pinfunction "2_2") (pintype "passive"))
      (node (ref "U2") (pin "15") (pinfunction "V3P3OUT_15") (pintype "passive"))
    )
    (net (code "54") (name "Net-(U2-VCP)") (class "Default")
      (node (ref "C2") (pin "2") (pinfunction "2_2") (pintype "passive"))
      (node (ref "U2") (pin "3") (pinfunction "VCP_3") (pintype "passive"))
    )
    (net (code "55") (name "Net-(U4-VBUS)") (class "Default")
      (node (ref "R17") (pin "1") (pinfunction "1_1") (pintype "passive"))
      (node (ref "U4") (pin "8") (pinfunction "VBUS_8") (pintype "passive"))
    )
    (net (code "56") (name "Net-(U4-VDD)") (class "Default")
      (node (ref "C11") (pin "2") (pinfunction "2_2") (pintype "passive"))
      (node (ref "R11") (pin "1") (pinfunction "1_1") (pintype "passive"))
      (node (ref "U4") (pin "1") (pinfunction "VDD_1") (pintype "passive"))
    )
    (net (code "57") (name "Net-(U6-BOOT)") (class "Default")
      (node (ref "C15") (pin "2") (pinfunction "2_2") (pintype "passive"))
      (node (ref "U6") (pin "1") (pinfunction "BOOT_1") (pintype "passive"))
    )
    (net (code "58") (name "Net-(U6-VSENSE)") (class "Default")
      (node (ref "R14") (pin "2") (pinfunction "2_2") (pintype "passive"))
      (node (ref "R20") (pin "2") (pinfunction "2_2") (pintype "passive"))
      (node (ref "U6") (pin "4") (pinfunction "VSENSE_4") (pintype "passive"))
    )
    (net (code "59") (name "Net-(U8-BOOT)") (class "Default")
      (node (ref "C19") (pin "2") (pinfunction "2_2") (pintype "passive"))
      (node (ref "U8") (pin "1") (pinfunction "BOOT_1") (pintype "passive"))
    )
    (net (code "60") (name "Net-(U8-VSENSE)") (class "Default")
      (node (ref "R18") (pin "2") (pinfunction "2_2") (pintype "passive"))
      (node (ref "R25") (pin "2") (pinfunction "2_2") (pintype "passive"))
      (node (ref "U8") (pin "4") (pinfunction "VSENSE_4") (pintype "passive"))
    )
    (net (code "61") (name "unconnected-(DATA-Pad12)") (class "Default")
      (node (ref "DATA") (pin "12") (pinfunction "12_12") (pintype "passive+no_connect"))
    )
    (net (code "62") (name "unconnected-(DATA-Pad13)") (class "Default")
      (node (ref "DATA") (pin "13") (pinfunction "13_13") (pintype "passive+no_connect"))
    )
    (net (code "63") (name "unconnected-(DATA-Pad14)") (class "Default")
      (node (ref "DATA") (pin "14") (pinfunction "14_14") (pintype "passive+no_connect"))
    )
    (net (code "64") (name "unconnected-(DATA-Pad15)") (class "Default")
      (node (ref "DATA") (pin "15") (pinfunction "15_15") (pintype "passive+no_connect"))
    )
    (net (code "65") (name "unconnected-(DATA-SBU1-PadA8)") (class "Default")
      (node (ref "DATA") (pin "A8") (pinfunction "SBU1_A8") (pintype "passive+no_connect"))
    )
    (net (code "66") (name "unconnected-(DATA-SBU2-PadB8)") (class "Default")
      (node (ref "DATA") (pin "B8") (pinfunction "SBU2_B8") (pintype "passive+no_connect"))
    )
    (net (code "67") (name "unconnected-(PD-DN1-PadA7)") (class "Default")
      (node (ref "PD") (pin "A7") (pinfunction "DN1_A7") (pintype "passive+no_connect"))
    )
    (net (code "68") (name "unconnected-(PD-DN2-PadB7)") (class "Default")
      (node (ref "PD") (pin "B7") (pinfunction "DN2_B7") (pintype "passive+no_connect"))
    )
    (net (code "69") (name "unconnected-(PD-DP1-PadA6)") (class "Default")
      (node (ref "PD") (pin "A6") (pinfunction "DP1_A6") (pintype "passive+no_connect"))
    )
    (net (code "70") (name "unconnected-(PD-DP2-PadB6)") (class "Default")
      (node (ref "PD") (pin "B6") (pinfunction "DP2_B6") (pintype "passive+no_connect"))
    )
    (net (code "71") (name "unconnected-(PD-Pad12)") (class "Default")
      (node (ref "PD") (pin "12") (pinfunction "12_12") (pintype "passive+no_connect"))
    )
    (net (code "72") (name "unconnected-(PD-Pad13)") (class "Default")
      (node (ref "PD") (pin "13") (pinfunction "13_13") (pintype "passive+no_connect"))
    )
    (net (code "73") (name "unconnected-(PD-Pad14)") (class "Default")
      (node (ref "PD") (pin "14") (pinfunction "14_14") (pintype "passive+no_connect"))
    )
    (net (code "74") (name "unconnected-(PD-Pad15)") (class "Default")
      (node (ref "PD") (pin "15") (pinfunction "15_15") (pintype "passive+no_connect"))
    )
    (net (code "75") (name "unconnected-(PD-SBU1-PadA8)") (class "Default")
      (node (ref "PD") (pin "A8") (pinfunction "SBU1_A8") (pintype "passive+no_connect"))
    )
    (net (code "76") (name "unconnected-(PD-SBU2-PadB8)") (class "Default")
      (node (ref "PD") (pin "B8") (pinfunction "SBU2_B8") (pintype "passive+no_connect"))
    )
    (net (code "77") (name "unconnected-(SYSFAN1-Pad3)") (class "Default")
      (node (ref "SYSFAN1") (pin "3") (pinfunction "3_3") (pintype "passive+no_connect"))
    )
    (net (code "78") (name "unconnected-(SYSFAN1-Pad4)") (class "Default")
      (node (ref "SYSFAN1") (pin "4") (pinfunction "4_4") (pintype "passive+no_connect"))
    )
    (net (code "79") (name "unconnected-(U1-EP-Pad17)") (class "Default")
      (node (ref "U1") (pin "17") (pinfunction "EP_17") (pintype "passive+no_connect"))
    )
    (net (code "80") (name "unconnected-(U1-NC-Pad1)") (class "Default")
      (node (ref "U1") (pin "1") (pinfunction "NC_1") (pintype "passive+no_connect"))
    )
    (net (code "81") (name "unconnected-(U1-NC-Pad2)") (class "Default")
      (node (ref "U1") (pin "2") (pinfunction "NC_2") (pintype "passive+no_connect"))
    )
    (net (code "82") (name "unconnected-(U1-NC-Pad3)") (class "Default")
      (node (ref "U1") (pin "3") (pinfunction "NC_3") (pintype "passive+no_connect"))
    )
    (net (code "83") (name "unconnected-(U1-NC-Pad4)") (class "Default")
      (node (ref "U1") (pin "4") (pinfunction "NC_4") (pintype "passive+no_connect"))
    )
    (net (code "84") (name "unconnected-(U1-NC-Pad10)") (class "Default")
      (node (ref "U1") (pin "10") (pinfunction "NC_10") (pintype "passive+no_connect"))
    )
    (net (code "85") (name "unconnected-(U1-OUT-Pad15)") (class "Default")
      (node (ref "U1") (pin "15") (pinfunction "OUT_15") (pintype "passive+no_connect"))
    )
    (net (code "86") (name "unconnected-(U1-PUSH-Pad5)") (class "Default")
      (node (ref "U1") (pin "5") (pinfunction "PUSH_5") (pintype "passive+no_connect"))
    )
    (net (code "87") (name "unconnected-(U1-U-Pad11)") (class "Default")
      (node (ref "U1") (pin "11") (pinfunction "U_11") (pintype "passive+no_connect"))
    )
    (net (code "88") (name "unconnected-(U1-V-Pad12)") (class "Default")
      (node (ref "U1") (pin "12") (pinfunction "V_12") (pintype "passive+no_connect"))
    )
    (net (code "89") (name "unconnected-(U1-W-Pad9)") (class "Default")
      (node (ref "U1") (pin "9") (pinfunction "W_9") (pintype "passive+no_connect"))
    )
    (net (code "90") (name "unconnected-(U2-COMPO#-Pad19)") (class "Default")
      (node (ref "U2") (pin "19") (pinfunction "COMPO#_19") (pintype "passive+no_connect"))
    )
    (net (code "91") (name "unconnected-(U2-NC-Pad21)") (class "Default")
      (node (ref "U2") (pin "21") (pinfunction "NC_21") (pintype "passive+no_connect"))
    )
    (net (code "92") (name "unconnected-(U4-CFG1-Pad9)") (class "Default")
      (node (ref "U4") (pin "9") (pinfunction "CFG1_9") (pintype "passive+no_connect"))
    )
    (net (code "93") (name "unconnected-(U4-CFG2-Pad2)") (class "Default")
      (node (ref "U4") (pin "2") (pinfunction "CFG2_2") (pintype "passive+no_connect"))
    )
    (net (code "94") (name "unconnected-(U4-CFG3-Pad3)") (class "Default")
      (node (ref "U4") (pin "3") (pinfunction "CFG3_3") (pintype "passive+no_connect"))
    )
    (net (code "95") (name "unconnected-(U4-DM-Pad5)") (class "Default")
      (node (ref "U4") (pin "5") (pinfunction "DM_5") (pintype "passive+no_connect"))
    )
    (net (code "96") (name "unconnected-(U4-DP-Pad4)") (class "Default")
      (node (ref "U4") (pin "4") (pinfunction "DP_4") (pintype "passive+no_connect"))
    )
    (net (code "97") (name "unconnected-(U4-PG-Pad10)") (class "Default")
      (node (ref "U4") (pin "10") (pinfunction "PG_10") (pintype "passive+no_connect"))
    )
    (net (code "98") (name "unconnected-(U5-IO15-Pad23)") (class "Default")
      (node (ref "U5") (pin "23") (pinfunction "IO15_23") (pintype "passive+no_connect"))
    )
    (net (code "99") (name "unconnected-(U5-IO32-Pad8)") (class "Default")
      (node (ref "U5") (pin "8") (pinfunction "IO32_8") (pintype "passive+no_connect"))
    )
    (net (code "100") (name "unconnected-(U5-IO34-Pad6)") (class "Default")
      (node (ref "U5") (pin "6") (pinfunction "IO34_6") (pintype "passive+no_connect"))
    )
    (net (code "101") (name "unconnected-(U5-IO35-Pad7)") (class "Default")
      (node (ref "U5") (pin "7") (pinfunction "IO35_7") (pintype "passive+no_connect"))
    )
    (net (code "102") (name "unconnected-(U5-NC-Pad17)") (class "Default")
      (node (ref "U5") (pin "17") (pinfunction "NC_17") (pintype "passive+no_connect"))
    )
    (net (code "103") (name "unconnected-(U5-NC-Pad18)") (class "Default")
      (node (ref "U5") (pin "18") (pinfunction "NC_18") (pintype "passive+no_connect"))
    )
    (net (code "104") (name "unconnected-(U5-NC-Pad19)") (class "Default")
      (node (ref "U5") (pin "19") (pinfunction "NC_19") (pintype "passive+no_connect"))
    )
    (net (code "105") (name "unconnected-(U5-NC-Pad20)") (class "Default")
      (node (ref "U5") (pin "20") (pinfunction "NC_20") (pintype "passive+no_connect"))
    )
    (net (code "106") (name "unconnected-(U5-NC-Pad21)") (class "Default")
      (node (ref "U5") (pin "21") (pinfunction "NC_21") (pintype "passive+no_connect"))
    )
    (net (code "107") (name "unconnected-(U5-NC-Pad22)") (class "Default")
      (node (ref "U5") (pin "22") (pinfunction "NC_22") (pintype "passive+no_connect"))
    )
    (net (code "108") (name "unconnected-(U5-NC-Pad32)") (class "Default")
      (node (ref "U5") (pin "32") (pinfunction "NC_32") (pintype "passive+no_connect"))
    )
    (net (code "109") (name "unconnected-(U5-SENSOR_VN-Pad5)") (class "Default")
      (node (ref "U5") (pin "5") (pinfunction "SENSOR_VN_5") (pintype "passive+no_connect"))
    )
    (net (code "110") (name "unconnected-(U5-SENSOR_VP-Pad4)") (class "Default")
      (node (ref "U5") (pin "4") (pinfunction "SENSOR_VP_4") (pintype "passive+no_connect"))
    )
    (net (code "111") (name "unconnected-(U6-ENA-Pad5)") (class "Default")
      (node (ref "U6") (pin "5") (pinfunction "ENA_5") (pintype "passive+no_connect"))
    )
    (net (code "112") (name "unconnected-(U6-NC-Pad2)") (class "Default")
      (node (ref "U6") (pin "2") (pinfunction "NC_2") (pintype "passive+no_connect"))
    )
    (net (code "113") (name "unconnected-(U6-NC-Pad3)") (class "Default")
      (node (ref "U6") (pin "3") (pinfunction "NC_3") (pintype "passive+no_connect"))
    )
    (net (code "114") (name "unconnected-(U7-CTS-Pad23)") (class "Default")
      (node (ref "U7") (pin "23") (pinfunction "CTS_23") (pintype "passive+no_connect"))
    )
    (net (code "115") (name "unconnected-(U7-DCD-Pad1)") (class "Default")
      (node (ref "U7") (pin "1") (pinfunction "DCD_1") (pintype "passive+no_connect"))
    )
    (net (code "116") (name "unconnected-(U7-DSR-Pad27)") (class "Default")
      (node (ref "U7") (pin "27") (pinfunction "DSR_27") (pintype "passive+no_connect"))
    )
    (net (code "117") (name "unconnected-(U7-NC-Pad10)") (class "Default")
      (node (ref "U7") (pin "10") (pinfunction "NC_10") (pintype "passive+no_connect"))
    )
    (net (code "118") (name "unconnected-(U7-NC-Pad13)") (class "Default")
      (node (ref "U7") (pin "13") (pinfunction "NC_13") (pintype "passive+no_connect"))
    )
    (net (code "119") (name "unconnected-(U7-NC-Pad14)") (class "Default")
      (node (ref "U7") (pin "14") (pinfunction "NC_14") (pintype "passive+no_connect"))
    )
    (net (code "120") (name "unconnected-(U7-NC-Pad15)") (class "Default")
      (node (ref "U7") (pin "15") (pinfunction "NC_15") (pintype "passive+no_connect"))
    )
    (net (code "121") (name "unconnected-(U7-NC-Pad16)") (class "Default")
      (node (ref "U7") (pin "16") (pinfunction "NC_16") (pintype "passive+no_connect"))
    )
    (net (code "122") (name "unconnected-(U7-NC-Pad17)") (class "Default")
      (node (ref "U7") (pin "17") (pinfunction "NC_17") (pintype "passive+no_connect"))
    )
    (net (code "123") (name "unconnected-(U7-NC-Pad18)") (class "Default")
      (node (ref "U7") (pin "18") (pinfunction "NC_18") (pintype "passive+no_connect"))
    )
    (net (code "124") (name "unconnected-(U7-NC-Pad19)") (class "Default")
      (node (ref "U7") (pin "19") (pinfunction "NC_19") (pintype "passive+no_connect"))
    )
    (net (code "125") (name "unconnected-(U7-NC-Pad20)") (class "Default")
      (node (ref "U7") (pin "20") (pinfunction "NC_20") (pintype "passive+no_connect"))
    )
    (net (code "126") (name "unconnected-(U7-NC-Pad21)") (class "Default")
      (node (ref "U7") (pin "21") (pinfunction "NC_21") (pintype "passive+no_connect"))
    )
    (net (code "127") (name "unconnected-(U7-NC-Pad22)") (class "Default")
      (node (ref "U7") (pin "22") (pinfunction "NC_22") (pintype "passive+no_connect"))
    )
    (net (code "128") (name "unconnected-(U7-RI-Pad2)") (class "Default")
      (node (ref "U7") (pin "2") (pinfunction "RI_2") (pintype "passive+no_connect"))
    )
    (net (code "129") (name "unconnected-(U7-SUSPEND#-Pad11)") (class "Default")
      (node (ref "U7") (pin "11") (pinfunction "SUSPEND#_11") (pintype "passive+no_connect"))
    )
    (net (code "130") (name "unconnected-(U7-SUSPEND-Pad12)") (class "Default")
      (node (ref "U7") (pin "12") (pinfunction "SUSPEND_12") (pintype "passive+no_connect"))
    )
    (net (code "131") (name "unconnected-(U8-ENA-Pad5)") (class "Default")
      (node (ref "U8") (pin "5") (pinfunction "ENA_5") (pintype "passive+no_connect"))
    )
    (net (code "132") (name "unconnected-(U8-NC-Pad2)") (class "Default")
      (node (ref "U8") (pin "2") (pinfunction "NC_2") (pintype "passive+no_connect"))
    )
    (net (code "133") (name "unconnected-(U8-NC-Pad3)") (class "Default")
      (node (ref "U8") (pin "3") (pinfunction "NC_3") (pintype "passive+no_connect"))
    )
  )
)
